# mainboard.net
KiCad netlist of a schematic drawn in Altium Designer
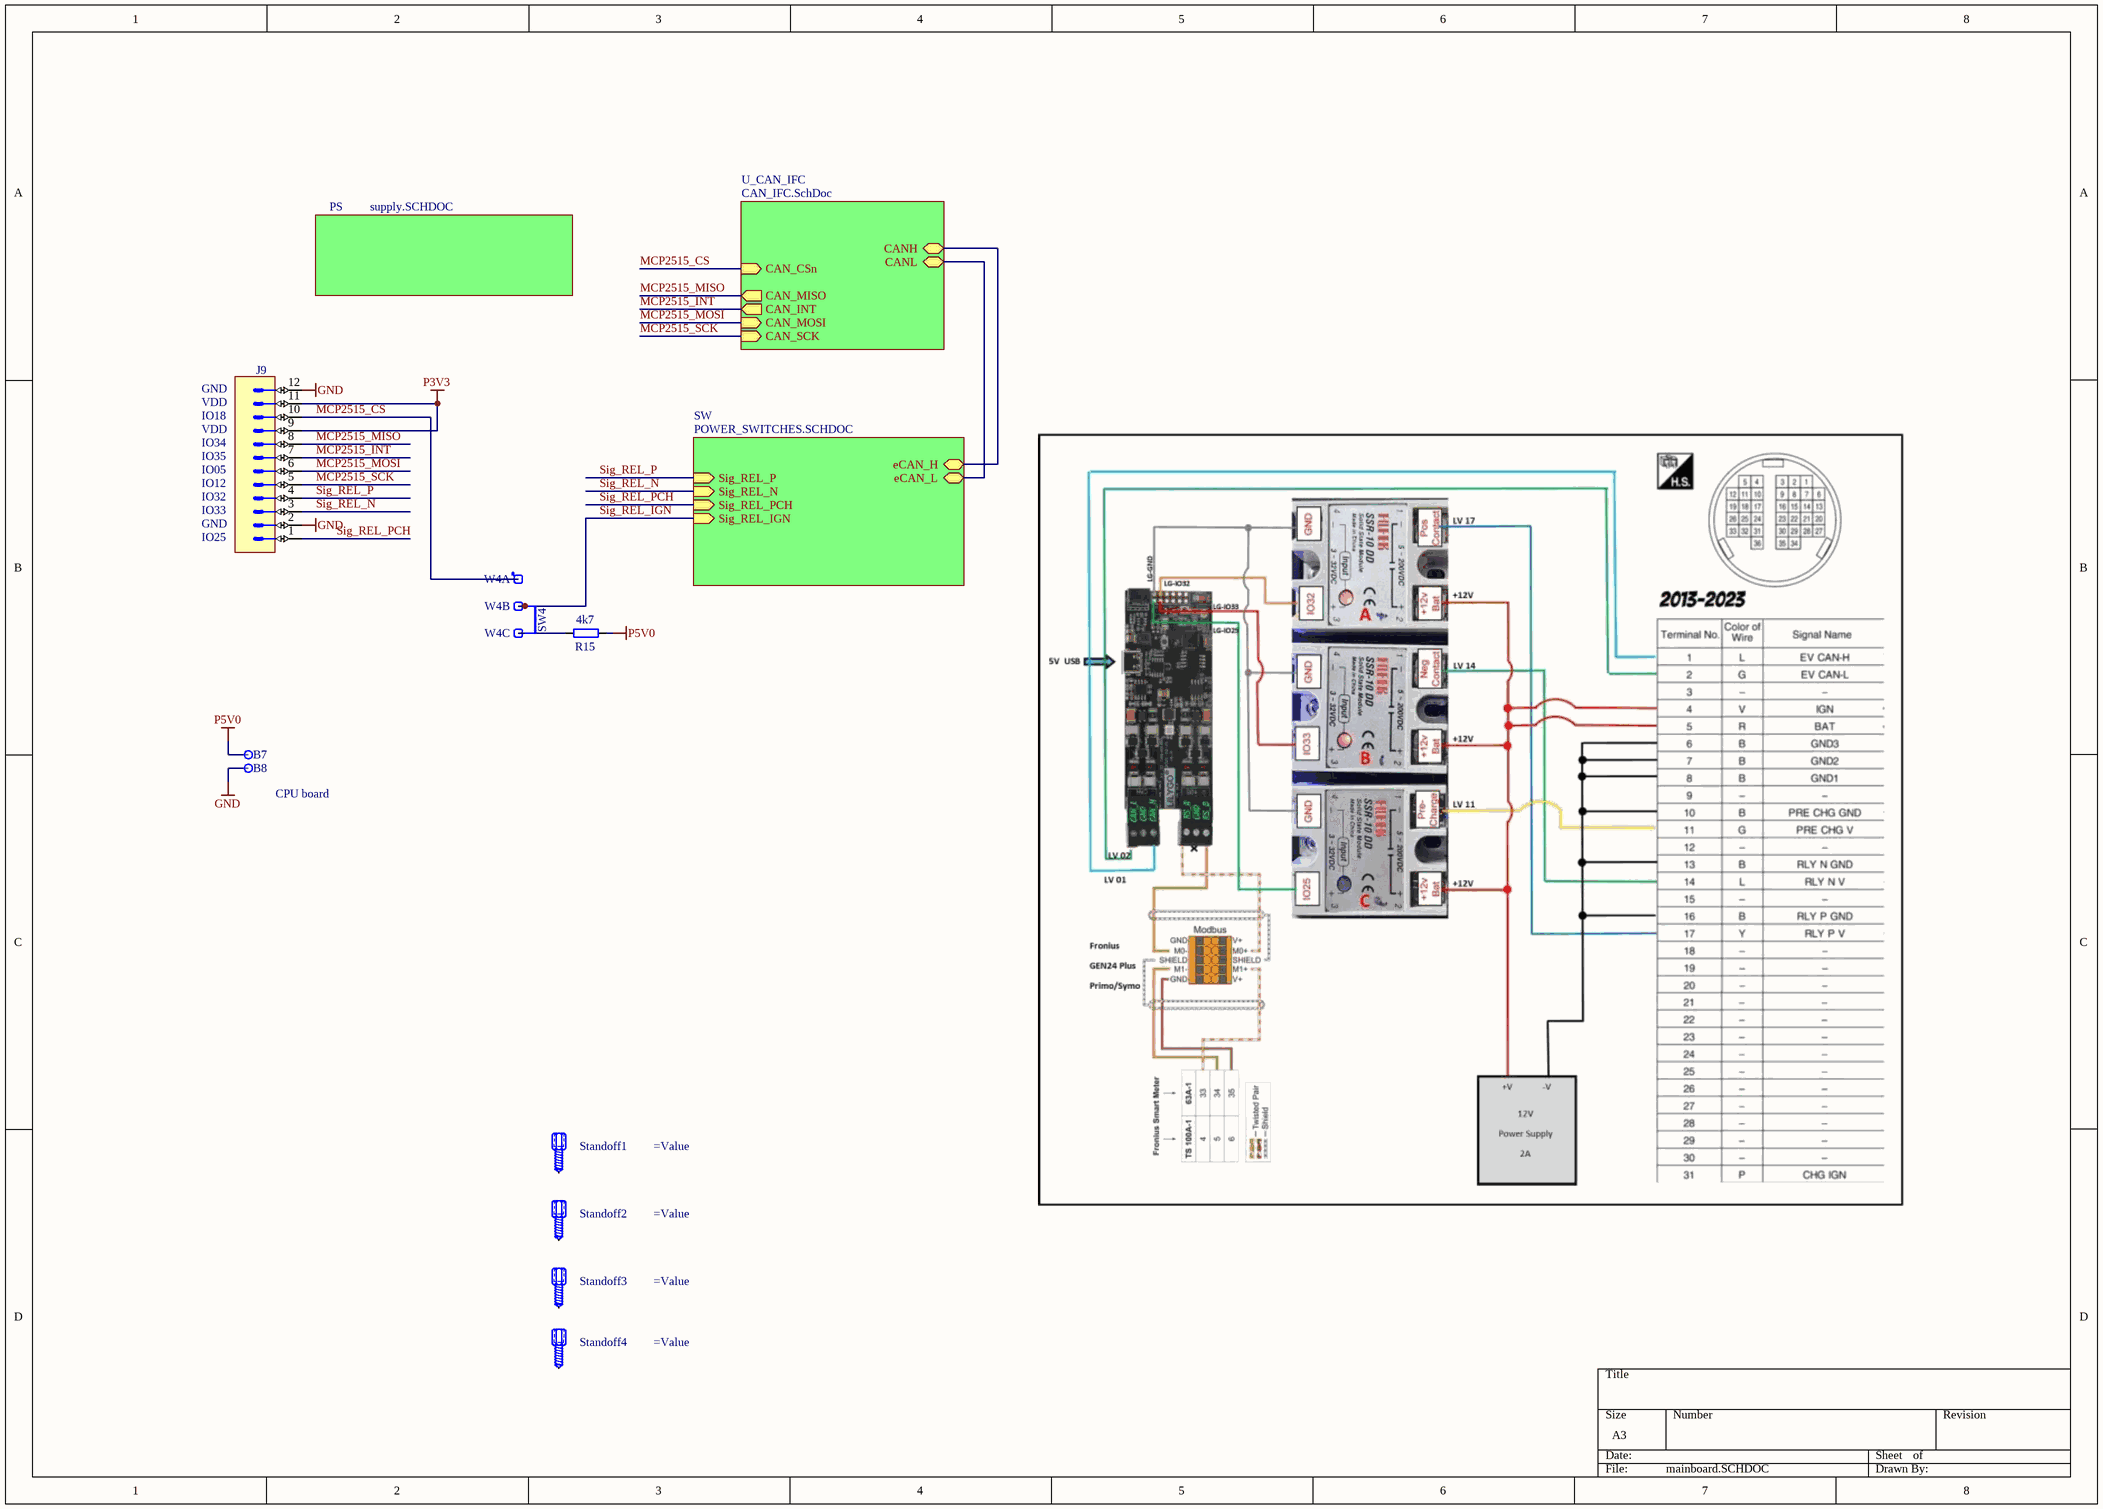
[diagram p0: mainboard.SCHDOC]

(export (version "E")
  (design (tool "Eeschema 10.0.6"))
  (components
    (comp (ref "B7")
      (value "Plated Hole")
      (footprint "c150h80")
      (description "Single Terminal Socket")
      (fields (field (name "PART NUMBER") "PLATED_HOLE0.8_PAD1.5") (field (name "AUTHOR") "CERN DEM JLC"))
      (libsource (lib "Eletro-mechanical") (part "Single Terminal Socket"))
    )
    (comp (ref "B8")
      (value "Plated Hole")
      (footprint "c150h80")
      (description "Single Terminal Socket")
      (fields (field (name "PART NUMBER") "PLATED_HOLE0.8_PAD1.5") (field (name "AUTHOR") "CERN DEM JLC"))
      (libsource (lib "Eletro-mechanical") (part "Single Terminal Socket"))
    )
    (comp (ref "J9")
      (value "Header 12")
      (footprint "SAMTEC_TSW-106-23-L-D")
      (description "Connector 12 Male")
      (fields
        (field (name "PART NUMBER") "SAMTEC_TSW-106-23-L-D")
        (field (name "MANUFACTURER") "SAMTEC")
        (field (name "AUTHOR") "CERN DEM MR")
      )
      (libsource (lib "Connectors") (part "Connector 12 Male"))
    )
    (comp (ref "R15")
      (value "4k7")
      (footprint "RESC1608X55N")
      (description "Resistor - 1%")
      (fields
        (field (name "PART NUMBER") "R0603_4K7_1%_0.1W_100PPM")
        (field (name "POWER") "0.1W")
        (field (name "AUTHOR") "CERN DEM JLC")
      )
      (libsource (lib "Resistors") (part "Resistor - 1%"))
    )
    (comp (ref "Standoff1")
      (value "~")
      (footprint "ETTINGER_005.13.113")
      (description "Standoff Male-Female")
      (fields
        (field (name "PART NUMBER") "ETTINGER_005.13.113")
        (field (name "MANUFACTURER") "ETTINGER")
        (field (name "AUTHOR") "CERN DEM HF")
      )
      (libsource (lib "Eletro-mechanical") (part "Standoff Male-Female"))
    )
    (comp (ref "Standoff2")
      (value "~")
      (footprint "ETTINGER_005.13.113")
      (description "Standoff Male-Female")
      (fields
        (field (name "PART NUMBER") "ETTINGER_005.13.113")
        (field (name "MANUFACTURER") "ETTINGER")
        (field (name "AUTHOR") "CERN DEM HF")
      )
      (libsource (lib "Eletro-mechanical") (part "Standoff Male-Female"))
    )
    (comp (ref "Standoff3")
      (value "~")
      (footprint "ETTINGER_005.13.113")
      (description "Standoff Male-Female")
      (fields
        (field (name "PART NUMBER") "ETTINGER_005.13.113")
        (field (name "MANUFACTURER") "ETTINGER")
        (field (name "AUTHOR") "CERN DEM HF")
      )
      (libsource (lib "Eletro-mechanical") (part "Standoff Male-Female"))
    )
    (comp (ref "Standoff4")
      (value "~")
      (footprint "ETTINGER_005.13.113")
      (description "Standoff Male-Female")
      (fields
        (field (name "PART NUMBER") "ETTINGER_005.13.113")
        (field (name "MANUFACTURER") "ETTINGER")
        (field (name "AUTHOR") "CERN DEM HF")
      )
      (libsource (lib "Eletro-mechanical") (part "Standoff Male-Female"))
    )
    (comp (ref "SW4")
      (value "Jumper Type1")
      (footprint "JUMPER_BLACK_INSULATED_2.54MM")
      (description "Jumper 1 Pin")
      (fields
        (field (name "PART NUMBER") "COMATEL_313.1730.0.00.40.0")
        (field (name "MANUFACTURER") "KONTEK COMATEL")
        (field (name "AUTHOR") "CERN DEM JLC")
      )
      (libsource (lib "Connectors") (part "Jumper Type1"))
    )
    (comp (ref "W4")
      (value "Test Point")
      (footprint "COMATEL_385.0358.1.03.400")
      (description "3 Mini Wire-Wrap Contact Strip Header")
      (fields
        (field (name "PART NUMBER") "COMATEL_385.0358.1.03.400")
        (field (name "MANUFACTURER") "KONTEK COMATEL")
        (field (name "AUTHOR") "CERN DEM JLC")
      )
      (libsource (lib "Connectors") (part "Wire-Wrap Contact x3"))
    )
  )
  (nets
    (net (code "3") (name "/MCP2515_CS") (class "Default")
      (node (ref "J9") (pin "10") (pinfunction "10_10") (pintype "bidirectional"))
      (node (ref "W4") (pin "1") (pinfunction "1_1") (pintype "bidirectional"))
    )
    (net (code "4") (name "/MCP2515_INT") (class "Default")
      (node (ref "J9") (pin "7") (pinfunction "7_7") (pintype "bidirectional"))
    )
    (net (code "5") (name "/MCP2515_MISO") (class "Default")
      (node (ref "J9") (pin "8") (pinfunction "8_8") (pintype "bidirectional"))
    )
    (net (code "6") (name "/MCP2515_MOSI") (class "Default")
      (node (ref "J9") (pin "6") (pinfunction "6_6") (pintype "bidirectional"))
    )
    (net (code "7") (name "/MCP2515_SCK") (class "Default")
      (node (ref "J9") (pin "5") (pinfunction "5_5") (pintype "bidirectional"))
    )
    (net (code "8") (name "/Sig_REL_IGN") (class "Default")
      (node (ref "SW4") (pin "1") (pinfunction "1_1") (pintype "bidirectional"))
      (node (ref "W4") (pin "2") (pinfunction "2_2") (pintype "bidirectional"))
    )
    (net (code "9") (name "/Sig_REL_N") (class "Default")
      (node (ref "J9") (pin "3") (pinfunction "3_3") (pintype "bidirectional"))
    )
    (net (code "10") (name "/Sig_REL_P") (class "Default")
      (node (ref "J9") (pin "4") (pinfunction "4_4") (pintype "bidirectional"))
    )
    (net (code "11") (name "/Sig_REL_PCH") (class "Default")
      (node (ref "J9") (pin "1") (pinfunction "1_1") (pintype "bidirectional"))
    )
    (net (code "12") (name "GND") (class "Default")
      (node (ref "B8") (pin "1") (pinfunction "1_1") (pintype "bidirectional"))
      (node (ref "J9") (pin "12") (pinfunction "12_12") (pintype "bidirectional"))
      (node (ref "J9") (pin "2") (pinfunction "2_2") (pintype "bidirectional"))
    )
    (net (code "13") (name "Net-(R15-Pad1)") (class "Default")
      (node (ref "R15") (pin "1") (pinfunction "1_1") (pintype "passive"))
      (node (ref "W4") (pin "3") (pinfunction "3_3") (pintype "bidirectional"))
    )
    (net (code "14") (name "P3V3") (class "Default")
      (node (ref "J9") (pin "11") (pinfunction "11_11") (pintype "bidirectional"))
      (node (ref "J9") (pin "9") (pinfunction "9_9") (pintype "bidirectional"))
    )
    (net (code "15") (name "P5V0") (class "Default")
      (node (ref "B7") (pin "1") (pinfunction "1_1") (pintype "bidirectional"))
      (node (ref "R15") (pin "2") (pinfunction "2_2") (pintype "passive"))
    )
    (net (code "16") (name "unconnected-(Standoff1-Pad1)") (class "Default")
      (node (ref "Standoff1") (pin "1") (pinfunction "1_1") (pintype "bidirectional"))
    )
    (net (code "17") (name "unconnected-(Standoff2-Pad1)") (class "Default")
      (node (ref "Standoff2") (pin "1") (pinfunction "1_1") (pintype "bidirectional"))
    )
    (net (code "18") (name "unconnected-(Standoff3-Pad1)") (class "Default")
      (node (ref "Standoff3") (pin "1") (pinfunction "1_1") (pintype "bidirectional"))
    )
    (net (code "19") (name "unconnected-(Standoff4-Pad1)") (class "Default")
      (node (ref "Standoff4") (pin "1") (pinfunction "1_1") (pintype "bidirectional"))
    )
  )
)
